# strip_controller.net
KiCad netlist of a schematic drawn in EAGLE
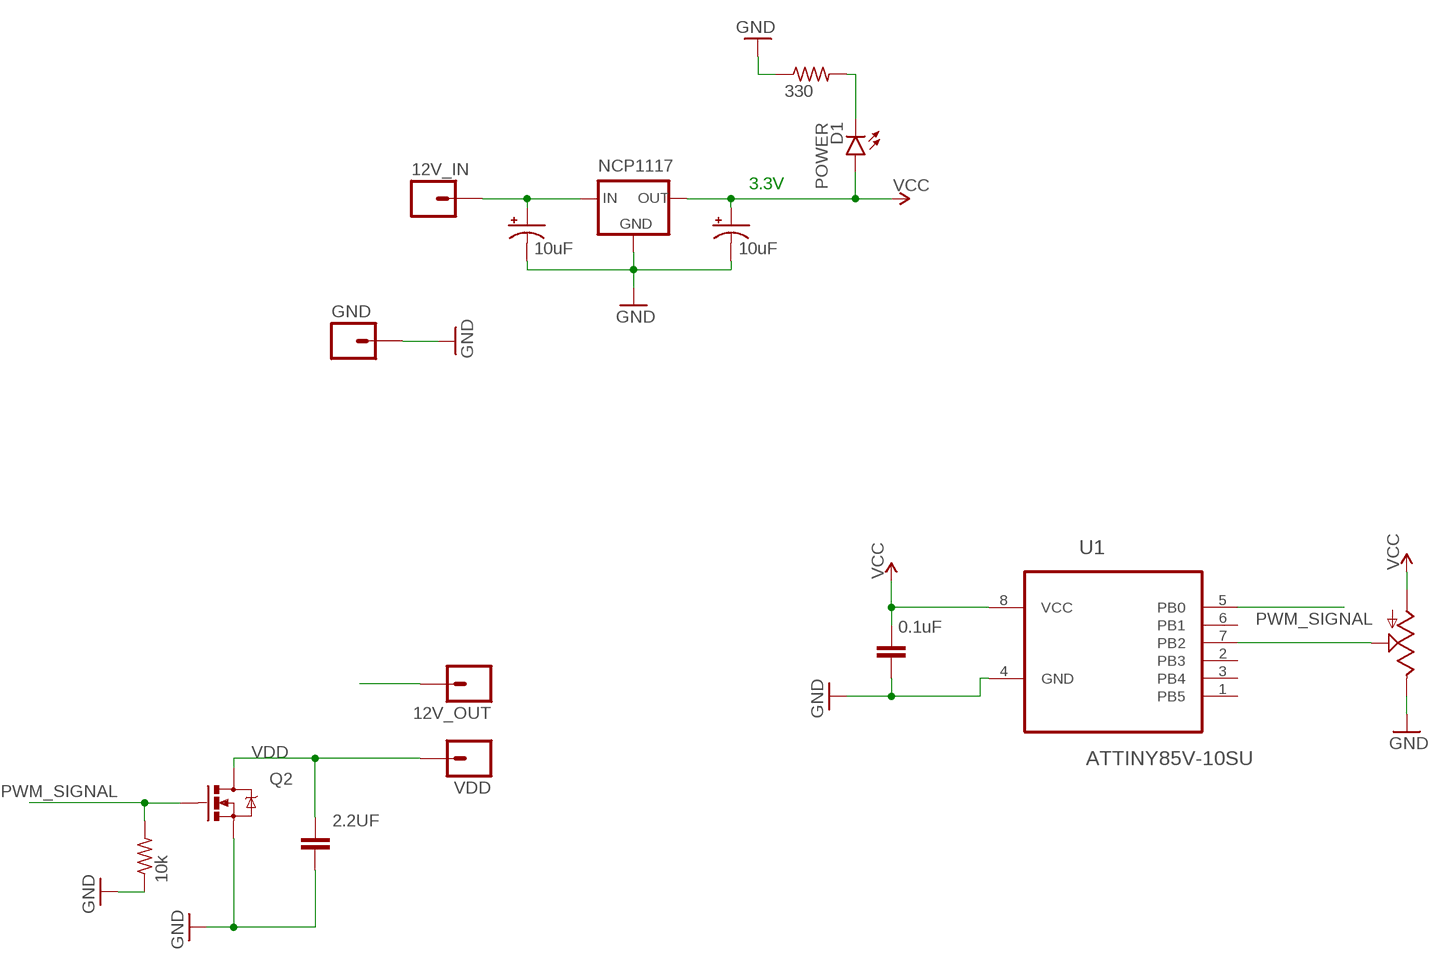
[diagram p0: schematic, sheet 1]

(export (version "E")
  (design (tool "Eeschema 10.0.6"))
  (components
    (comp (ref "12V_IN")
      (value "WAGO_2060M01")
      (footprint "eagle-import:WAGO_2060")
      (libsource (lib "eagle-import") (part "WAGO_2060M01"))
    )
    (comp (ref "12V_OUT")
      (value "WAGO_2060M01")
      (footprint "eagle-import:WAGO_2060")
      (libsource (lib "eagle-import") (part "WAGO_2060M01"))
    )
    (comp (ref "C2")
      (value "0.1uF")
      (footprint "eagle-import:0805")
      (libsource (lib "eagle-import") (part "CAP0805"))
    )
    (comp (ref "C4")
      (value "2.2UF")
      (footprint "eagle-import:1206")
      (libsource (lib "eagle-import") (part "2.2UF50V10%(1206)"))
    )
    (comp (ref "C5")
      (value "10uF")
      (footprint "eagle-import:CAP-PANASONIC-C")
      (libsource (lib "eagle-import") (part "CAP-POLCAP-PANASONIC-C"))
    )
    (comp (ref "C7")
      (value "10uF")
      (footprint "eagle-import:CAP-PANASONIC-C")
      (libsource (lib "eagle-import") (part "CAP-POLCAP-PANASONIC-C"))
    )
    (comp (ref "D1")
      (value "POWER")
      (footprint "eagle-import:LED-0603")
      (libsource (lib "eagle-import") (part "LED-GREEN0603"))
    )
    (comp (ref "GND")
      (value "WAGO_2060M01")
      (footprint "eagle-import:WAGO_2060")
      (libsource (lib "eagle-import") (part "WAGO_2060M01"))
    )
    (comp (ref "NCP1117")
      (value "VREG-3.3VNCP1117")
      (footprint "eagle-import:TO-252")
      (libsource (lib "eagle-import") (part "VREG-3.3VNCP1117"))
    )
    (comp (ref "Q2")
      (value "MOSFET-NCHANNELFDD8780")
      (footprint "eagle-import:DPAK")
      (libsource (lib "eagle-import") (part "MOSFET-NCHANNELFDD8780"))
    )
    (comp (ref "U$2")
      (value "BOURNS_SLIDE_POT")
      (footprint "eagle-import:BOURN_SLIDE_POT")
      (libsource (lib "eagle-import") (part "BOURNS_SLIDE_POT"))
    )
    (comp (ref "U$3")
      (value "330")
      (footprint "eagle-import:RESISTOR-0805")
      (libsource (lib "eagle-import") (part "RESISTOR"))
    )
    (comp (ref "U$15")
      (value "10k")
      (footprint "eagle-import:RESISTOR-0805")
      (libsource (lib "eagle-import") (part "RESISTOR"))
    )
    (comp (ref "U1")
      (value "ATTINY85V-10SU")
      (footprint "eagle-import:SOIC127P798X216-8N")
      (libsource (lib "eagle-import") (part "ATTINY85V-10SU"))
    )
    (comp (ref "VDD")
      (value "WAGO_2060M01")
      (footprint "eagle-import:WAGO_2060")
      (libsource (lib "eagle-import") (part "WAGO_2060M01"))
    )
  )
  (nets
    (net (code "1") (name "/12V") (class "Default")
      (node (ref "12V_IN") (pin "L1.2") (pinfunction "1_L1.2") (pintype "passive"))
      (node (ref "12V_OUT") (pin "L1.2") (pinfunction "1_L1.2") (pintype "passive"))
      (node (ref "C5") (pin "+") (pinfunction "+_+") (pintype "passive"))
      (node (ref "NCP1117") (pin "3") (pinfunction "IN_3") (pintype "input"))
    )
    (net (code "2") (name "/PWM_SIGNAL") (class "Default")
      (node (ref "Q2") (pin "1") (pinfunction "G_1") (pintype "passive"))
      (node (ref "U$15") (pin "2") (pinfunction "2_2") (pintype "passive"))
      (node (ref "U1") (pin "5") (pinfunction "PB0_5") (pintype "bidirectional"))
    )
    (net (code "3") (name "/VDD") (class "Default")
      (node (ref "C4") (pin "2") (pinfunction "2_2") (pintype "passive"))
      (node (ref "Q2") (pin "4") (pinfunction "D_4") (pintype "passive"))
      (node (ref "VDD") (pin "L1.2") (pinfunction "1_L1.2") (pintype "passive"))
    )
    (net (code "4") (name "GND") (class "Default")
      (node (ref "C2") (pin "2") (pinfunction "2_2") (pintype "passive"))
      (node (ref "C4") (pin "1") (pinfunction "1_1") (pintype "passive"))
      (node (ref "C5") (pin "-") (pinfunction "-_-") (pintype "passive"))
      (node (ref "C7") (pin "-") (pinfunction "-_-") (pintype "passive"))
      (node (ref "GND") (pin "L1.2") (pinfunction "1_L1.2") (pintype "passive"))
      (node (ref "NCP1117") (pin "1") (pinfunction "GND_1") (pintype "input"))
      (node (ref "Q2") (pin "3") (pinfunction "S_3") (pintype "passive"))
      (node (ref "U$15") (pin "1") (pinfunction "1_1") (pintype "passive"))
      (node (ref "U$2") (pin "P$7") (pinfunction "3_P$7") (pintype "passive"))
      (node (ref "U$3") (pin "1") (pinfunction "1_1") (pintype "passive"))
      (node (ref "U1") (pin "4") (pinfunction "GND_4") (pintype "passive"))
    )
    (net (code "5") (name "Net-(D1-PadC)") (class "Default")
      (node (ref "D1") (pin "C") (pinfunction "C_C") (pintype "passive"))
      (node (ref "U$3") (pin "2") (pinfunction "2_2") (pintype "passive"))
    )
    (net (code "6") (name "Net-(U$2-2)") (class "Default")
      (node (ref "U$2") (pin "P$5") (pinfunction "2_P$5") (pintype "passive"))
      (node (ref "U1") (pin "7") (pinfunction "PB2_7") (pintype "bidirectional"))
    )
    (net (code "7") (name "VCC") (class "Default")
      (node (ref "C2") (pin "1") (pinfunction "1_1") (pintype "passive"))
      (node (ref "C7") (pin "+") (pinfunction "+_+") (pintype "passive"))
      (node (ref "D1") (pin "A") (pinfunction "A_A") (pintype "passive"))
      (node (ref "NCP1117") (pin "2") (pinfunction "OUT_2") (pintype "passive"))
      (node (ref "U$2") (pin "P$6") (pinfunction "1_P$6") (pintype "passive"))
      (node (ref "U1") (pin "8") (pinfunction "VCC_8") (pintype "power_in"))
    )
    (net (code "8") (name "unconnected-(U1-PB1-Pad6)") (class "Default")
      (node (ref "U1") (pin "6") (pinfunction "PB1_6") (pintype "bidirectional"))
    )
    (net (code "9") (name "unconnected-(U1-PB3-Pad2)") (class "Default")
      (node (ref "U1") (pin "2") (pinfunction "PB3_2") (pintype "bidirectional"))
    )
    (net (code "10") (name "unconnected-(U1-PB4-Pad3)") (class "Default")
      (node (ref "U1") (pin "3") (pinfunction "PB4_3") (pintype "bidirectional"))
    )
    (net (code "11") (name "unconnected-(U1-PB5-Pad1)") (class "Default")
      (node (ref "U1") (pin "1") (pinfunction "PB5_1") (pintype "bidirectional"))
    )
  )
)
